# Sheet1.net
KiCad netlist of a schematic drawn in Altium Designer
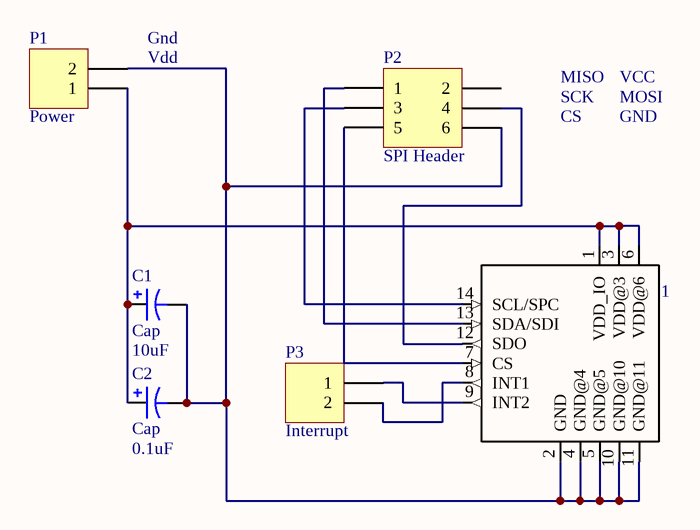
[diagram p0: Sheet1.SchDoc]

(export (version "E")
  (design (tool "Eeschema 10.0.6"))
  (components
    (comp (ref "1")
      (value "LIS302DL")
      (footprint "LGA14_LIS302DL(Primary)")
      (libsource (lib "LIS302DL") (part "LIS302DL"))
    )
    (comp (ref "C1")
      (value "Cap")
      (footprint "C0805")
      (description "Polarized Capacitor (Surface Mount)")
      (fields (field (name "ALTIUM_VALUE") "10uF") (field (name "PUBLISHER") "Altium Limited"))
      (libsource (lib "Miscellaneous Devices") (part "Cap Pol3"))
    )
    (comp (ref "C2")
      (value "Cap")
      (footprint "C0805")
      (description "Polarized Capacitor (Surface Mount)")
      (fields (field (name "ALTIUM_VALUE") "0.1uF") (field (name "PUBLISHER") "Altium Limited"))
      (libsource (lib "Miscellaneous Devices") (part "Cap Pol3"))
    )
    (comp (ref "P1")
      (value "Power")
      (footprint "HDR1X2")
      (description "Header, 2-Pin")
      (fields (field (name "PUBLISHER") "Altium Limited"))
      (libsource (lib "") (part "Header 2_1"))
    )
    (comp (ref "P2")
      (value "SPI Header")
      (footprint "HDR2X3")
      (description "Header, 3-Pin, Dual row")
      (fields (field (name "PUBLISHER") "Altium Limited"))
      (libsource (lib "Miscellaneous Connectors") (part "Header 3X2"))
    )
    (comp (ref "P3")
      (value "Interrupt")
      (footprint "HDR1X2")
      (description "Header, 2-Pin")
      (fields (field (name "PUBLISHER") "Altium Limited"))
      (libsource (lib "Miscellaneous Connectors") (part "Header 2"))
    )
  )
  (nets
    (net (code "1") (name "Net-(1-CS)") (class "Default")
      (node (ref "1") (pin "7") (pinfunction "CS_7") (pintype "input"))
      (node (ref "P2") (pin "5") (pinfunction "5_5") (pintype "passive"))
    )
    (net (code "2") (name "Net-(1-GND)") (class "Default")
      (node (ref "1") (pin "10") (pinfunction "GND@10_10") (pintype "power_in"))
      (node (ref "1") (pin "11") (pinfunction "GND@11_11") (pintype "power_in"))
      (node (ref "1") (pin "2") (pinfunction "GND_2") (pintype "power_in"))
      (node (ref "1") (pin "4") (pinfunction "GND@4_4") (pintype "power_in"))
      (node (ref "1") (pin "5") (pinfunction "GND@5_5") (pintype "power_in"))
      (node (ref "C1") (pin "2") (pinfunction "2_2") (pintype "passive"))
      (node (ref "C2") (pin "2") (pinfunction "2_2") (pintype "passive"))
      (node (ref "P1") (pin "2") (pinfunction "2_2") (pintype "passive"))
      (node (ref "P2") (pin "6") (pinfunction "6_6") (pintype "passive"))
    )
    (net (code "3") (name "Net-(1-INT1)") (class "Default")
      (node (ref "1") (pin "8") (pinfunction "INT1_8") (pintype "output"))
      (node (ref "P3") (pin "2") (pinfunction "2_2") (pintype "passive"))
    )
    (net (code "4") (name "Net-(1-INT2)") (class "Default")
      (node (ref "1") (pin "9") (pinfunction "INT2_9") (pintype "output"))
      (node (ref "P3") (pin "1") (pinfunction "1_1") (pintype "passive"))
    )
    (net (code "5") (name "Net-(1-SCL{slash}SPC)") (class "Default")
      (node (ref "1") (pin "14") (pinfunction "SCL/SPC_14") (pintype "input"))
      (node (ref "P2") (pin "3") (pinfunction "3_3") (pintype "passive"))
    )
    (net (code "6") (name "Net-(1-SDA{slash}SDI)") (class "Default")
      (node (ref "1") (pin "13") (pinfunction "SDA/SDI_13") (pintype "input"))
      (node (ref "P2") (pin "1") (pinfunction "1_1") (pintype "passive"))
    )
    (net (code "7") (name "Net-(1-SDO)") (class "Default")
      (node (ref "1") (pin "12") (pinfunction "SDO_12") (pintype "output"))
      (node (ref "P2") (pin "4") (pinfunction "4_4") (pintype "passive"))
    )
    (net (code "8") (name "Net-(1-VDD@3)") (class "Default")
      (node (ref "1") (pin "1") (pinfunction "VDD_IO_1") (pintype "power_in"))
      (node (ref "1") (pin "3") (pinfunction "VDD@3_3") (pintype "power_in"))
      (node (ref "1") (pin "6") (pinfunction "VDD@6_6") (pintype "power_in"))
      (node (ref "C1") (pin "1") (pinfunction "1_1") (pintype "passive"))
      (node (ref "C2") (pin "1") (pinfunction "1_1") (pintype "passive"))
      (node (ref "P1") (pin "1") (pinfunction "1_1") (pintype "passive"))
    )
    (net (code "9") (name "unconnected-(P2-Pad2)") (class "Default")
      (node (ref "P2") (pin "2") (pinfunction "2_2") (pintype "passive"))
    )
  )
)
